# cv-utils.net
KiCad netlist of a schematic drawn in EAGLE
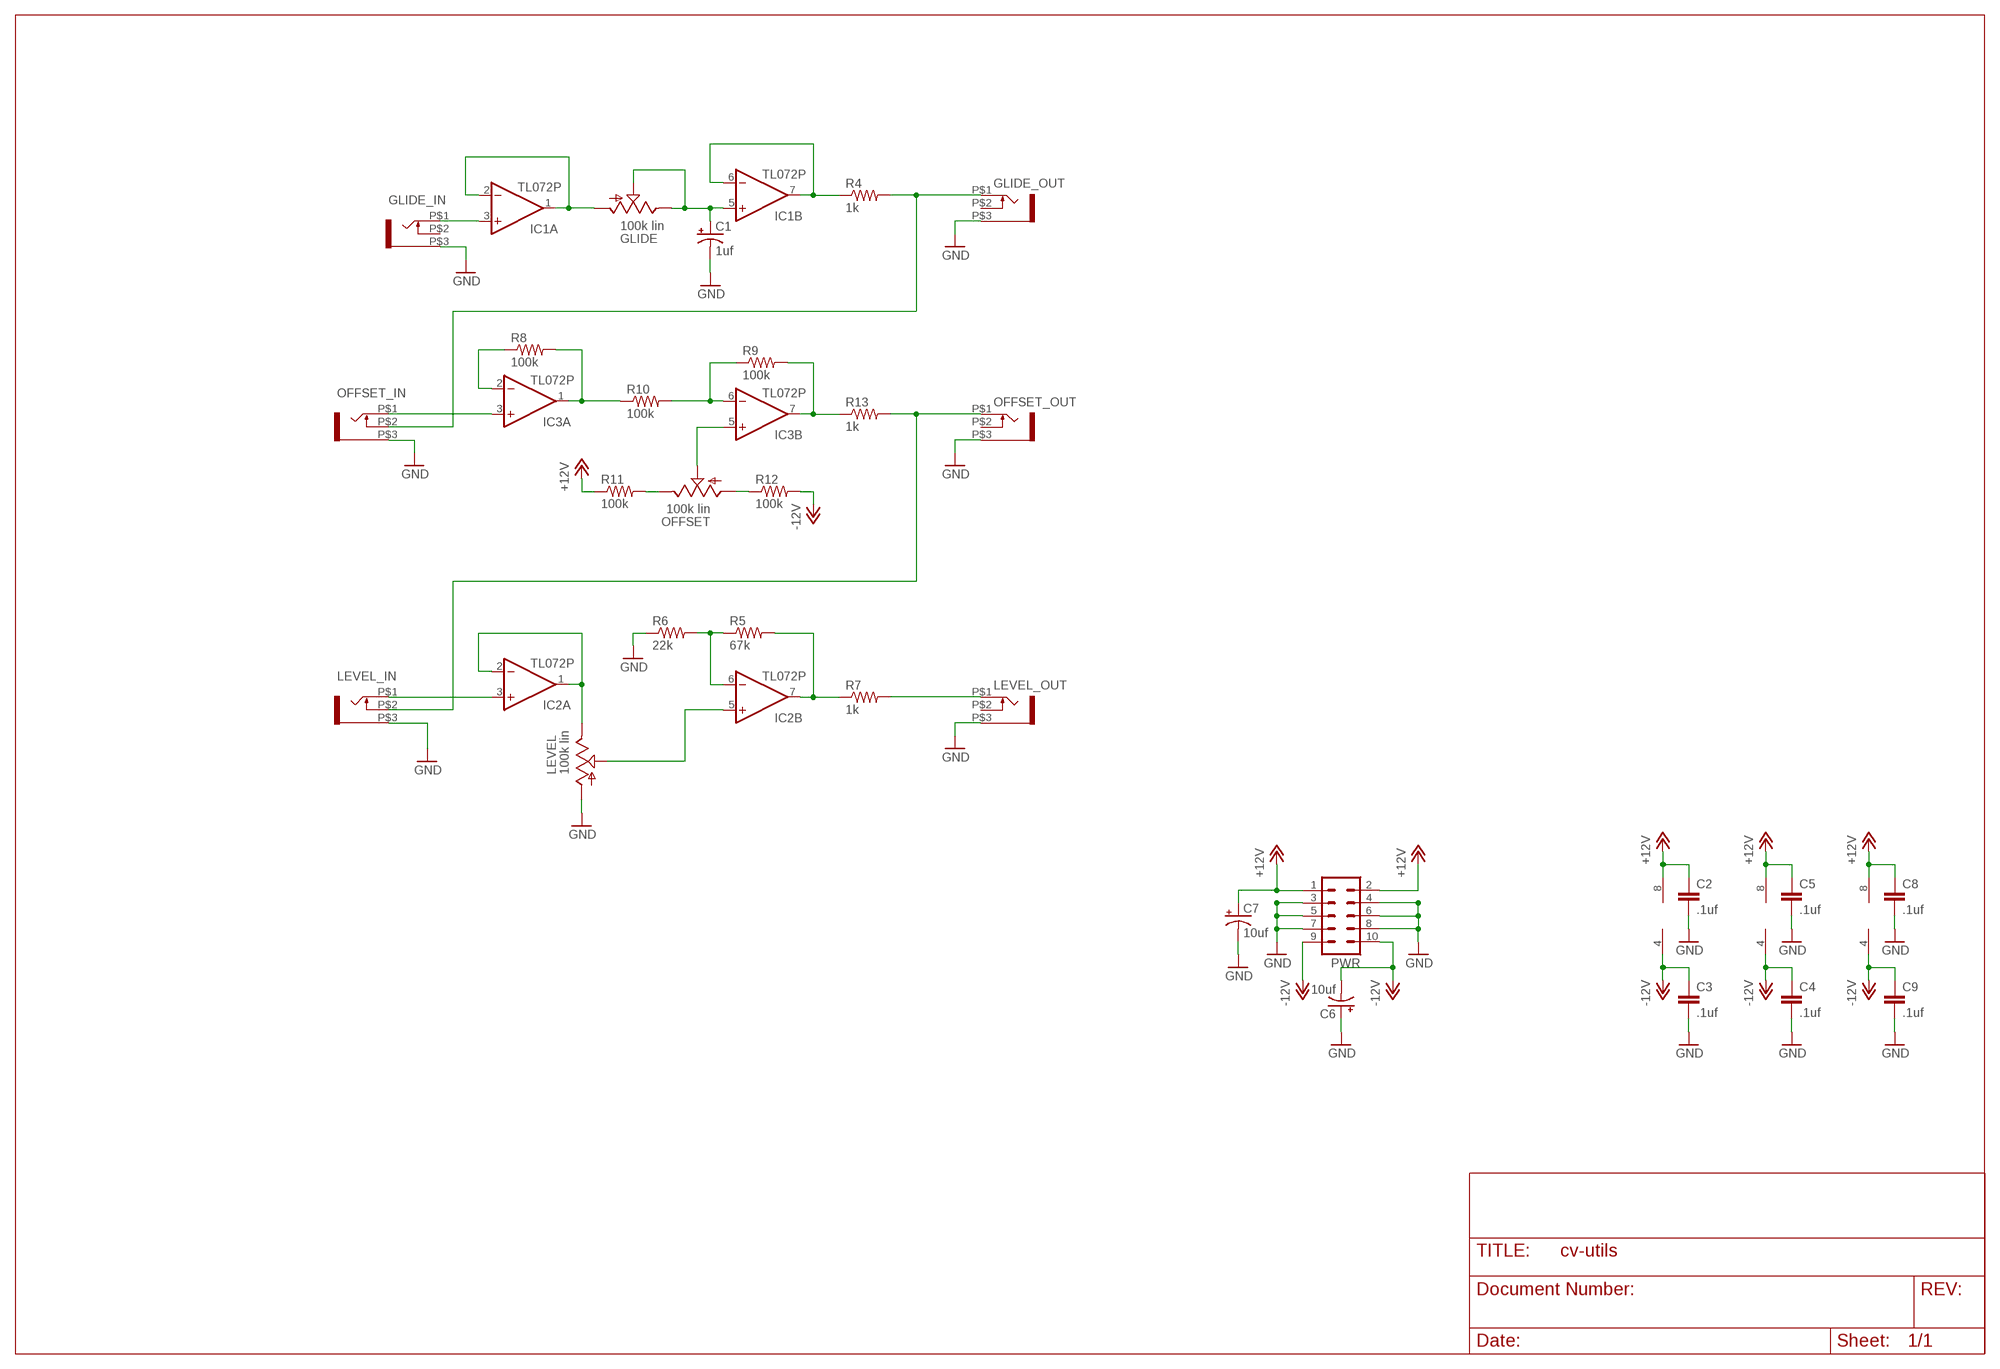
[diagram p0: schematic, sheet 1]

(export (version "E")
  (design (tool "Eeschema 10.0.6"))
  (components
    (comp (ref "C1")
      (value "1uf")
      (footprint "eagle-import:E2,5-6")
      (libsource (lib "eagle-import") (part "CPOL-USE2.5-6"))
    )
    (comp (ref "C2")
      (value ".1uf")
      (footprint "eagle-import:C050-024X044")
      (libsource (lib "eagle-import") (part "C-EU050-024X044"))
    )
    (comp (ref "C3")
      (value ".1uf")
      (footprint "eagle-import:C050-024X044")
      (libsource (lib "eagle-import") (part "C-EU050-024X044"))
    )
    (comp (ref "C4")
      (value ".1uf")
      (footprint "eagle-import:C050-024X044")
      (libsource (lib "eagle-import") (part "C-EU050-024X044"))
    )
    (comp (ref "C5")
      (value ".1uf")
      (footprint "eagle-import:C050-024X044")
      (libsource (lib "eagle-import") (part "C-EU050-024X044"))
    )
    (comp (ref "C6")
      (value "10uf")
      (footprint "eagle-import:E2,5-5")
      (libsource (lib "eagle-import") (part "CPOL-USE2.5-5"))
    )
    (comp (ref "C7")
      (value "10uf")
      (footprint "eagle-import:E2,5-5")
      (libsource (lib "eagle-import") (part "CPOL-USE2.5-5"))
    )
    (comp (ref "C8")
      (value ".1uf")
      (footprint "eagle-import:C050-024X044")
      (libsource (lib "eagle-import") (part "C-EU050-024X044"))
    )
    (comp (ref "C9")
      (value ".1uf")
      (footprint "eagle-import:C050-024X044")
      (libsource (lib "eagle-import") (part "C-EU050-024X044"))
    )
    (comp (ref "GLIDE")
      (value "100k lin")
      (footprint "eagle-import:EVUF")
      (libsource (lib "eagle-import") (part "ALPHA-9MMA"))
    )
    (comp (ref "GLIDE_IN")
      (value "WQP-PJ301M-12_JACK")
      (footprint "eagle-import:WQP-PJ301M-12_JACK")
      (libsource (lib "eagle-import") (part "WQP-PJ301M-12_JACK"))
    )
    (comp (ref "GLIDE_OUT")
      (value "WQP-PJ301M-12_JACK")
      (footprint "eagle-import:WQP-PJ301M-12_JACK")
      (libsource (lib "eagle-import") (part "WQP-PJ301M-12_JACK"))
    )
    (comp (ref "IC1")
      (value "TL072P")
      (footprint "eagle-import:DIL08")
      (libsource (lib "eagle-import") (part "TL072P"))
    )
    (comp (ref "IC2")
      (value "TL072P")
      (footprint "eagle-import:DIL08")
      (libsource (lib "eagle-import") (part "TL072P"))
    )
    (comp (ref "IC3")
      (value "TL072P")
      (footprint "eagle-import:DIL08")
      (libsource (lib "eagle-import") (part "TL072P"))
    )
    (comp (ref "LEVEL")
      (value "100k lin")
      (footprint "eagle-import:EVUF")
      (libsource (lib "eagle-import") (part "ALPHA-9MMA"))
    )
    (comp (ref "LEVEL_IN")
      (value "WQP-PJ301M-12_JACK")
      (footprint "eagle-import:WQP-PJ301M-12_JACK")
      (libsource (lib "eagle-import") (part "WQP-PJ301M-12_JACK"))
    )
    (comp (ref "LEVEL_OUT")
      (value "WQP-PJ301M-12_JACK")
      (footprint "eagle-import:WQP-PJ301M-12_JACK")
      (libsource (lib "eagle-import") (part "WQP-PJ301M-12_JACK"))
    )
    (comp (ref "OFFSET")
      (value "100k lin")
      (footprint "eagle-import:EVUF")
      (libsource (lib "eagle-import") (part "ALPHA-9MMA"))
    )
    (comp (ref "OFFSET_IN")
      (value "WQP-PJ301M-12_JACK")
      (footprint "eagle-import:WQP-PJ301M-12_JACK")
      (libsource (lib "eagle-import") (part "WQP-PJ301M-12_JACK"))
    )
    (comp (ref "OFFSET_OUT")
      (value "WQP-PJ301M-12_JACK")
      (footprint "eagle-import:WQP-PJ301M-12_JACK")
      (libsource (lib "eagle-import") (part "WQP-PJ301M-12_JACK"))
    )
    (comp (ref "PWR")
      (value "ML10")
      (footprint "eagle-import:ML10")
      (libsource (lib "eagle-import") (part "ML10"))
    )
    (comp (ref "R4")
      (value "1k")
      (footprint "eagle-import:0204_7")
      (libsource (lib "eagle-import") (part "R-US_0204/7"))
    )
    (comp (ref "R5")
      (value "67k")
      (footprint "eagle-import:0204_7")
      (libsource (lib "eagle-import") (part "R-US_0204/7"))
    )
    (comp (ref "R6")
      (value "22k")
      (footprint "eagle-import:0204_7")
      (libsource (lib "eagle-import") (part "R-US_0204/7"))
    )
    (comp (ref "R7")
      (value "1k")
      (footprint "eagle-import:0204_7")
      (libsource (lib "eagle-import") (part "R-US_0204/7"))
    )
    (comp (ref "R8")
      (value "100k")
      (footprint "eagle-import:0204_7")
      (libsource (lib "eagle-import") (part "R-US_0204/7"))
    )
    (comp (ref "R9")
      (value "100k")
      (footprint "eagle-import:0204_7")
      (libsource (lib "eagle-import") (part "R-US_0204/7"))
    )
    (comp (ref "R10")
      (value "100k")
      (footprint "eagle-import:0204_7")
      (libsource (lib "eagle-import") (part "R-US_0204/7"))
    )
    (comp (ref "R11")
      (value "100k")
      (footprint "eagle-import:0204_7")
      (libsource (lib "eagle-import") (part "R-US_0204/7"))
    )
    (comp (ref "R12")
      (value "100k")
      (footprint "eagle-import:0204_7")
      (libsource (lib "eagle-import") (part "R-US_0204/7"))
    )
    (comp (ref "R13")
      (value "1k")
      (footprint "eagle-import:0204_7")
      (libsource (lib "eagle-import") (part "R-US_0204/7"))
    )
  )
  (nets
    (net (code "1") (name "+12V") (class "Default")
      (node (ref "C2") (pin "1") (pinfunction "1_1") (pintype "passive"))
      (node (ref "C5") (pin "1") (pinfunction "1_1") (pintype "passive"))
      (node (ref "C7") (pin "+") (pinfunction "+_+") (pintype "passive"))
      (node (ref "C8") (pin "1") (pinfunction "1_1") (pintype "passive"))
      (node (ref "IC1") (pin "8") (pinfunction "V+_8") (pintype "power_in"))
      (node (ref "IC2") (pin "8") (pinfunction "V+_8") (pintype "power_in"))
      (node (ref "IC3") (pin "8") (pinfunction "V+_8") (pintype "power_in"))
      (node (ref "PWR") (pin "1") (pinfunction "1_1") (pintype "passive"))
      (node (ref "PWR") (pin "2") (pinfunction "2_2") (pintype "passive"))
      (node (ref "R11") (pin "1") (pinfunction "1_1") (pintype "passive"))
    )
    (net (code "2") (name "-12V") (class "Default")
      (node (ref "C3") (pin "1") (pinfunction "1_1") (pintype "passive"))
      (node (ref "C4") (pin "1") (pinfunction "1_1") (pintype "passive"))
      (node (ref "C6") (pin "-") (pinfunction "-_-") (pintype "passive"))
      (node (ref "C9") (pin "1") (pinfunction "1_1") (pintype "passive"))
      (node (ref "IC1") (pin "4") (pinfunction "V-_4") (pintype "power_in"))
      (node (ref "IC2") (pin "4") (pinfunction "V-_4") (pintype "power_in"))
      (node (ref "IC3") (pin "4") (pinfunction "V-_4") (pintype "power_in"))
      (node (ref "PWR") (pin "10") (pinfunction "10_10") (pintype "passive"))
      (node (ref "PWR") (pin "9") (pinfunction "9_9") (pintype "passive"))
      (node (ref "R12") (pin "2") (pinfunction "2_2") (pintype "passive"))
    )
    (net (code "3") (name "GND") (class "Default")
      (node (ref "C1") (pin "-") (pinfunction "-_-") (pintype "passive"))
      (node (ref "C2") (pin "2") (pinfunction "2_2") (pintype "passive"))
      (node (ref "C3") (pin "2") (pinfunction "2_2") (pintype "passive"))
      (node (ref "C4") (pin "2") (pinfunction "2_2") (pintype "passive"))
      (node (ref "C5") (pin "2") (pinfunction "2_2") (pintype "passive"))
      (node (ref "C6") (pin "+") (pinfunction "+_+") (pintype "passive"))
      (node (ref "C7") (pin "-") (pinfunction "-_-") (pintype "passive"))
      (node (ref "C8") (pin "2") (pinfunction "2_2") (pintype "passive"))
      (node (ref "C9") (pin "2") (pinfunction "2_2") (pintype "passive"))
      (node (ref "GLIDE_IN") (pin "P$3") (pinfunction "1_P$3") (pintype "passive"))
      (node (ref "GLIDE_OUT") (pin "P$3") (pinfunction "1_P$3") (pintype "passive"))
      (node (ref "LEVEL") (pin "1") (pinfunction "A_1") (pintype "passive"))
      (node (ref "LEVEL_IN") (pin "P$3") (pinfunction "1_P$3") (pintype "passive"))
      (node (ref "LEVEL_OUT") (pin "P$3") (pinfunction "1_P$3") (pintype "passive"))
      (node (ref "OFFSET_IN") (pin "P$3") (pinfunction "1_P$3") (pintype "passive"))
      (node (ref "OFFSET_OUT") (pin "P$3") (pinfunction "1_P$3") (pintype "passive"))
      (node (ref "PWR") (pin "3") (pinfunction "3_3") (pintype "passive"))
      (node (ref "PWR") (pin "4") (pinfunction "4_4") (pintype "passive"))
      (node (ref "PWR") (pin "5") (pinfunction "5_5") (pintype "passive"))
      (node (ref "PWR") (pin "6") (pinfunction "6_6") (pintype "passive"))
      (node (ref "PWR") (pin "7") (pinfunction "7_7") (pintype "passive"))
      (node (ref "PWR") (pin "8") (pinfunction "8_8") (pintype "passive"))
      (node (ref "R6") (pin "1") (pinfunction "1_1") (pintype "passive"))
    )
    (net (code "4") (name "Net-(GLIDE-A)") (class "Default")
      (node (ref "GLIDE") (pin "1") (pinfunction "A_1") (pintype "passive"))
      (node (ref "IC1") (pin "1") (pinfunction "OUT_1") (pintype "output"))
      (node (ref "IC1") (pin "2") (pinfunction "-IN_2") (pintype "input"))
    )
    (net (code "5") (name "Net-(GLIDE-E)") (class "Default")
      (node (ref "C1") (pin "+") (pinfunction "+_+") (pintype "passive"))
      (node (ref "GLIDE") (pin "2") (pinfunction "S_2") (pintype "passive"))
      (node (ref "GLIDE") (pin "3") (pinfunction "E_3") (pintype "passive"))
      (node (ref "IC1") (pin "5") (pinfunction "+IN_5") (pintype "input"))
    )
    (net (code "6") (name "Net-(GLIDE_IN-2)") (class "Default")
      (node (ref "GLIDE_IN") (pin "P$1") (pinfunction "2_P$1") (pintype "passive"))
      (node (ref "IC1") (pin "3") (pinfunction "+IN_3") (pintype "input"))
    )
    (net (code "7") (name "Net-(GLIDE_OUT-2)") (class "Default")
      (node (ref "GLIDE_OUT") (pin "P$1") (pinfunction "2_P$1") (pintype "passive"))
      (node (ref "OFFSET_IN") (pin "P$2") (pinfunction "3_P$2") (pintype "passive"))
      (node (ref "R4") (pin "2") (pinfunction "2_2") (pintype "passive"))
    )
    (net (code "8") (name "Net-(IC1B--IN)") (class "Default")
      (node (ref "IC1") (pin "6") (pinfunction "-IN_6") (pintype "input"))
      (node (ref "IC1") (pin "7") (pinfunction "OUT_7") (pintype "output"))
      (node (ref "R4") (pin "1") (pinfunction "1_1") (pintype "passive"))
    )
    (net (code "9") (name "Net-(IC2A-+IN)") (class "Default")
      (node (ref "IC2") (pin "3") (pinfunction "+IN_3") (pintype "input"))
      (node (ref "LEVEL_IN") (pin "P$1") (pinfunction "2_P$1") (pintype "passive"))
    )
    (net (code "10") (name "Net-(IC2A--IN)") (class "Default")
      (node (ref "IC2") (pin "1") (pinfunction "OUT_1") (pintype "output"))
      (node (ref "IC2") (pin "2") (pinfunction "-IN_2") (pintype "input"))
      (node (ref "LEVEL") (pin "3") (pinfunction "E_3") (pintype "passive"))
    )
    (net (code "11") (name "Net-(IC2B-+IN)") (class "Default")
      (node (ref "IC2") (pin "5") (pinfunction "+IN_5") (pintype "input"))
      (node (ref "LEVEL") (pin "2") (pinfunction "S_2") (pintype "passive"))
    )
    (net (code "12") (name "Net-(IC2B--IN)") (class "Default")
      (node (ref "IC2") (pin "6") (pinfunction "-IN_6") (pintype "input"))
      (node (ref "R5") (pin "1") (pinfunction "1_1") (pintype "passive"))
      (node (ref "R6") (pin "2") (pinfunction "2_2") (pintype "passive"))
    )
    (net (code "13") (name "Net-(IC2B-OUT)") (class "Default")
      (node (ref "IC2") (pin "7") (pinfunction "OUT_7") (pintype "output"))
      (node (ref "R5") (pin "2") (pinfunction "2_2") (pintype "passive"))
      (node (ref "R7") (pin "1") (pinfunction "1_1") (pintype "passive"))
    )
    (net (code "14") (name "Net-(IC3A-+IN)") (class "Default")
      (node (ref "IC3") (pin "3") (pinfunction "+IN_3") (pintype "input"))
      (node (ref "OFFSET_IN") (pin "P$1") (pinfunction "2_P$1") (pintype "passive"))
    )
    (net (code "15") (name "Net-(IC3A--IN)") (class "Default")
      (node (ref "IC3") (pin "2") (pinfunction "-IN_2") (pintype "input"))
      (node (ref "R8") (pin "1") (pinfunction "1_1") (pintype "passive"))
    )
    (net (code "16") (name "Net-(IC3A-OUT)") (class "Default")
      (node (ref "IC3") (pin "1") (pinfunction "OUT_1") (pintype "output"))
      (node (ref "R10") (pin "1") (pinfunction "1_1") (pintype "passive"))
      (node (ref "R8") (pin "2") (pinfunction "2_2") (pintype "passive"))
    )
    (net (code "17") (name "Net-(IC3B-+IN)") (class "Default")
      (node (ref "IC3") (pin "5") (pinfunction "+IN_5") (pintype "input"))
      (node (ref "OFFSET") (pin "2") (pinfunction "S_2") (pintype "passive"))
    )
    (net (code "18") (name "Net-(IC3B--IN)") (class "Default")
      (node (ref "IC3") (pin "6") (pinfunction "-IN_6") (pintype "input"))
      (node (ref "R10") (pin "2") (pinfunction "2_2") (pintype "passive"))
      (node (ref "R9") (pin "1") (pinfunction "1_1") (pintype "passive"))
    )
    (net (code "19") (name "Net-(IC3B-OUT)") (class "Default")
      (node (ref "IC3") (pin "7") (pinfunction "OUT_7") (pintype "output"))
      (node (ref "R13") (pin "1") (pinfunction "1_1") (pintype "passive"))
      (node (ref "R9") (pin "2") (pinfunction "2_2") (pintype "passive"))
    )
    (net (code "20") (name "Net-(LEVEL_IN-3)") (class "Default")
      (node (ref "LEVEL_IN") (pin "P$2") (pinfunction "3_P$2") (pintype "passive"))
      (node (ref "OFFSET_OUT") (pin "P$1") (pinfunction "2_P$1") (pintype "passive"))
      (node (ref "R13") (pin "2") (pinfunction "2_2") (pintype "passive"))
    )
    (net (code "21") (name "Net-(LEVEL_OUT-2)") (class "Default")
      (node (ref "LEVEL_OUT") (pin "P$1") (pinfunction "2_P$1") (pintype "passive"))
      (node (ref "R7") (pin "2") (pinfunction "2_2") (pintype "passive"))
    )
    (net (code "22") (name "Net-(OFFSET-A)") (class "Default")
      (node (ref "OFFSET") (pin "1") (pinfunction "A_1") (pintype "passive"))
      (node (ref "R12") (pin "1") (pinfunction "1_1") (pintype "passive"))
    )
    (net (code "23") (name "Net-(OFFSET-E)") (class "Default")
      (node (ref "OFFSET") (pin "3") (pinfunction "E_3") (pintype "passive"))
      (node (ref "R11") (pin "2") (pinfunction "2_2") (pintype "passive"))
    )
    (net (code "24") (name "unconnected-(GLIDE_IN-3-PadP$2)") (class "Default")
      (node (ref "GLIDE_IN") (pin "P$2") (pinfunction "3_P$2") (pintype "passive"))
    )
    (net (code "25") (name "unconnected-(GLIDE_OUT-3-PadP$2)") (class "Default")
      (node (ref "GLIDE_OUT") (pin "P$2") (pinfunction "3_P$2") (pintype "passive"))
    )
    (net (code "26") (name "unconnected-(LEVEL_OUT-3-PadP$2)") (class "Default")
      (node (ref "LEVEL_OUT") (pin "P$2") (pinfunction "3_P$2") (pintype "passive"))
    )
    (net (code "27") (name "unconnected-(OFFSET_OUT-3-PadP$2)") (class "Default")
      (node (ref "OFFSET_OUT") (pin "P$2") (pinfunction "3_P$2") (pintype "passive"))
    )
  )
)
